# Relais.net
KiCad netlist of a schematic drawn in Altium Designer
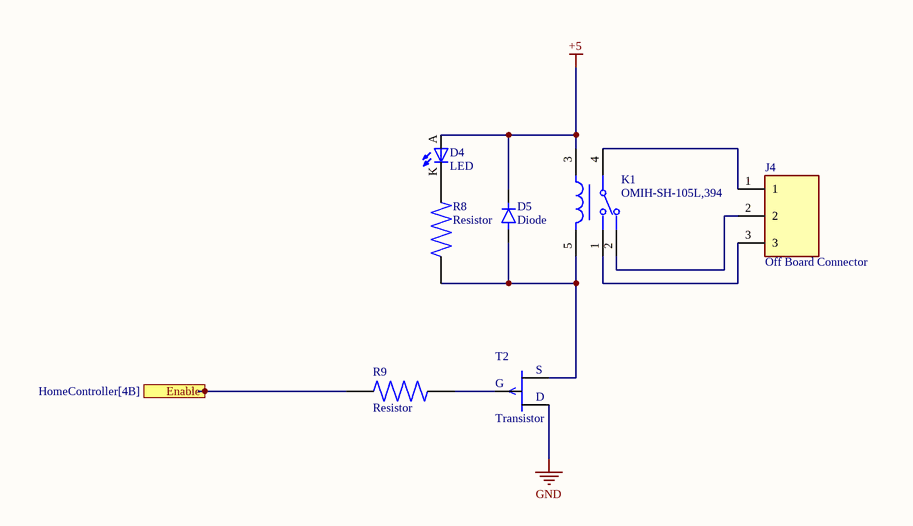
[diagram p0: Relais.SchDoc]

(export (version "E")
  (design (tool "Eeschema 10.0.6"))
  (components
    (comp (ref "D4")
      (value "LED")
      (footprint "New footprint 1")
      (description "3mm LED")
      (libsource (lib "Tobias") (part "3mm LED"))
    )
    (comp (ref "D5")
      (value "Diode")
      (footprint "Diode-Footprint-1")
      (description "Generic Diode")
      (libsource (lib "Tobias") (part "Diode-Symbol-1"))
    )
    (comp (ref "J4")
      (value "Off Board Connector")
      (footprint "Off Board Connector-Footprint-1")
      (description "3 Pin")
      (libsource (lib "Tobias") (part "Off Board Connector-Symbol-1"))
    )
    (comp (ref "K1")
      (value "OMIH-SH-105L,394")
      (footprint "FP-OMIH-SH-105L_394-MFG")
      (libsource (lib "Tobias") (part "9326bfaabe3e5fa933881ff237cda8c"))
    )
    (comp (ref "R8")
      (value "Resistor")
      (footprint "Resistor-Footprint-1")
      (description "Generic Resistor")
      (libsource (lib "Tobias") (part "Resistor-Symbol-1"))
    )
    (comp (ref "R9")
      (value "Resistor")
      (footprint "Resistor-Footprint-1")
      (description "Generic Resistor")
      (libsource (lib "Tobias") (part "Resistor-Symbol-1"))
    )
    (comp (ref "T2")
      (value "Transistor")
      (footprint "Transistor-Footprint-1")
      (description "Generic Transistor")
      (libsource (lib "Tobias") (part "Transistor-Symbol-1"))
    )
  )
  (nets
    (net (code "1") (name "+5") (class "Default")
      (node (ref "D4") (pin "A") (pinfunction "A_A") (pintype "passive"))
      (node (ref "D5") (pin "K") (pinfunction "K_K") (pintype "passive"))
      (node (ref "K1") (pin "3") (pinfunction "3_3") (pintype "passive"))
    )
    (net (code "2") (name "/Enable") (class "Default")
      (node (ref "R9") (pin "1") (pinfunction "1_1") (pintype "passive"))
    )
    (net (code "3") (name "GND") (class "Default")
      (node (ref "T2") (pin "2") (pinfunction "D_2") (pintype "passive"))
    )
    (net (code "4") (name "Net-(D4-PadK)") (class "Default")
      (node (ref "D4") (pin "K") (pinfunction "K_K") (pintype "passive"))
      (node (ref "R8") (pin "2") (pinfunction "2_2") (pintype "passive"))
    )
    (net (code "5") (name "Net-(J4-Pad1)") (class "Default")
      (node (ref "J4") (pin "1") (pinfunction "1_1") (pintype "passive"))
      (node (ref "K1") (pin "4") (pinfunction "4_4") (pintype "passive"))
    )
    (net (code "6") (name "Net-(J4-Pad2)") (class "Default")
      (node (ref "J4") (pin "2") (pinfunction "2_2") (pintype "passive"))
      (node (ref "K1") (pin "2") (pinfunction "2_2") (pintype "passive"))
    )
    (net (code "7") (name "Net-(J4-Pad3)") (class "Default")
      (node (ref "J4") (pin "3") (pinfunction "3_3") (pintype "passive"))
      (node (ref "K1") (pin "1") (pinfunction "1_1") (pintype "passive"))
    )
    (net (code "8") (name "Net-(T2-G)") (class "Default")
      (node (ref "R9") (pin "2") (pinfunction "2_2") (pintype "passive"))
      (node (ref "T2") (pin "3") (pinfunction "G_3") (pintype "passive"))
    )
    (net (code "9") (name "Net-(T2-S)") (class "Default")
      (node (ref "D5") (pin "A") (pinfunction "A_A") (pintype "passive"))
      (node (ref "K1") (pin "5") (pinfunction "5_5") (pintype "passive"))
      (node (ref "R8") (pin "1") (pinfunction "1_1") (pintype "passive"))
      (node (ref "T2") (pin "1") (pinfunction "S_1") (pintype "passive"))
    )
  )
)
